# waveform_shield.net
KiCad netlist of a schematic drawn in EAGLE
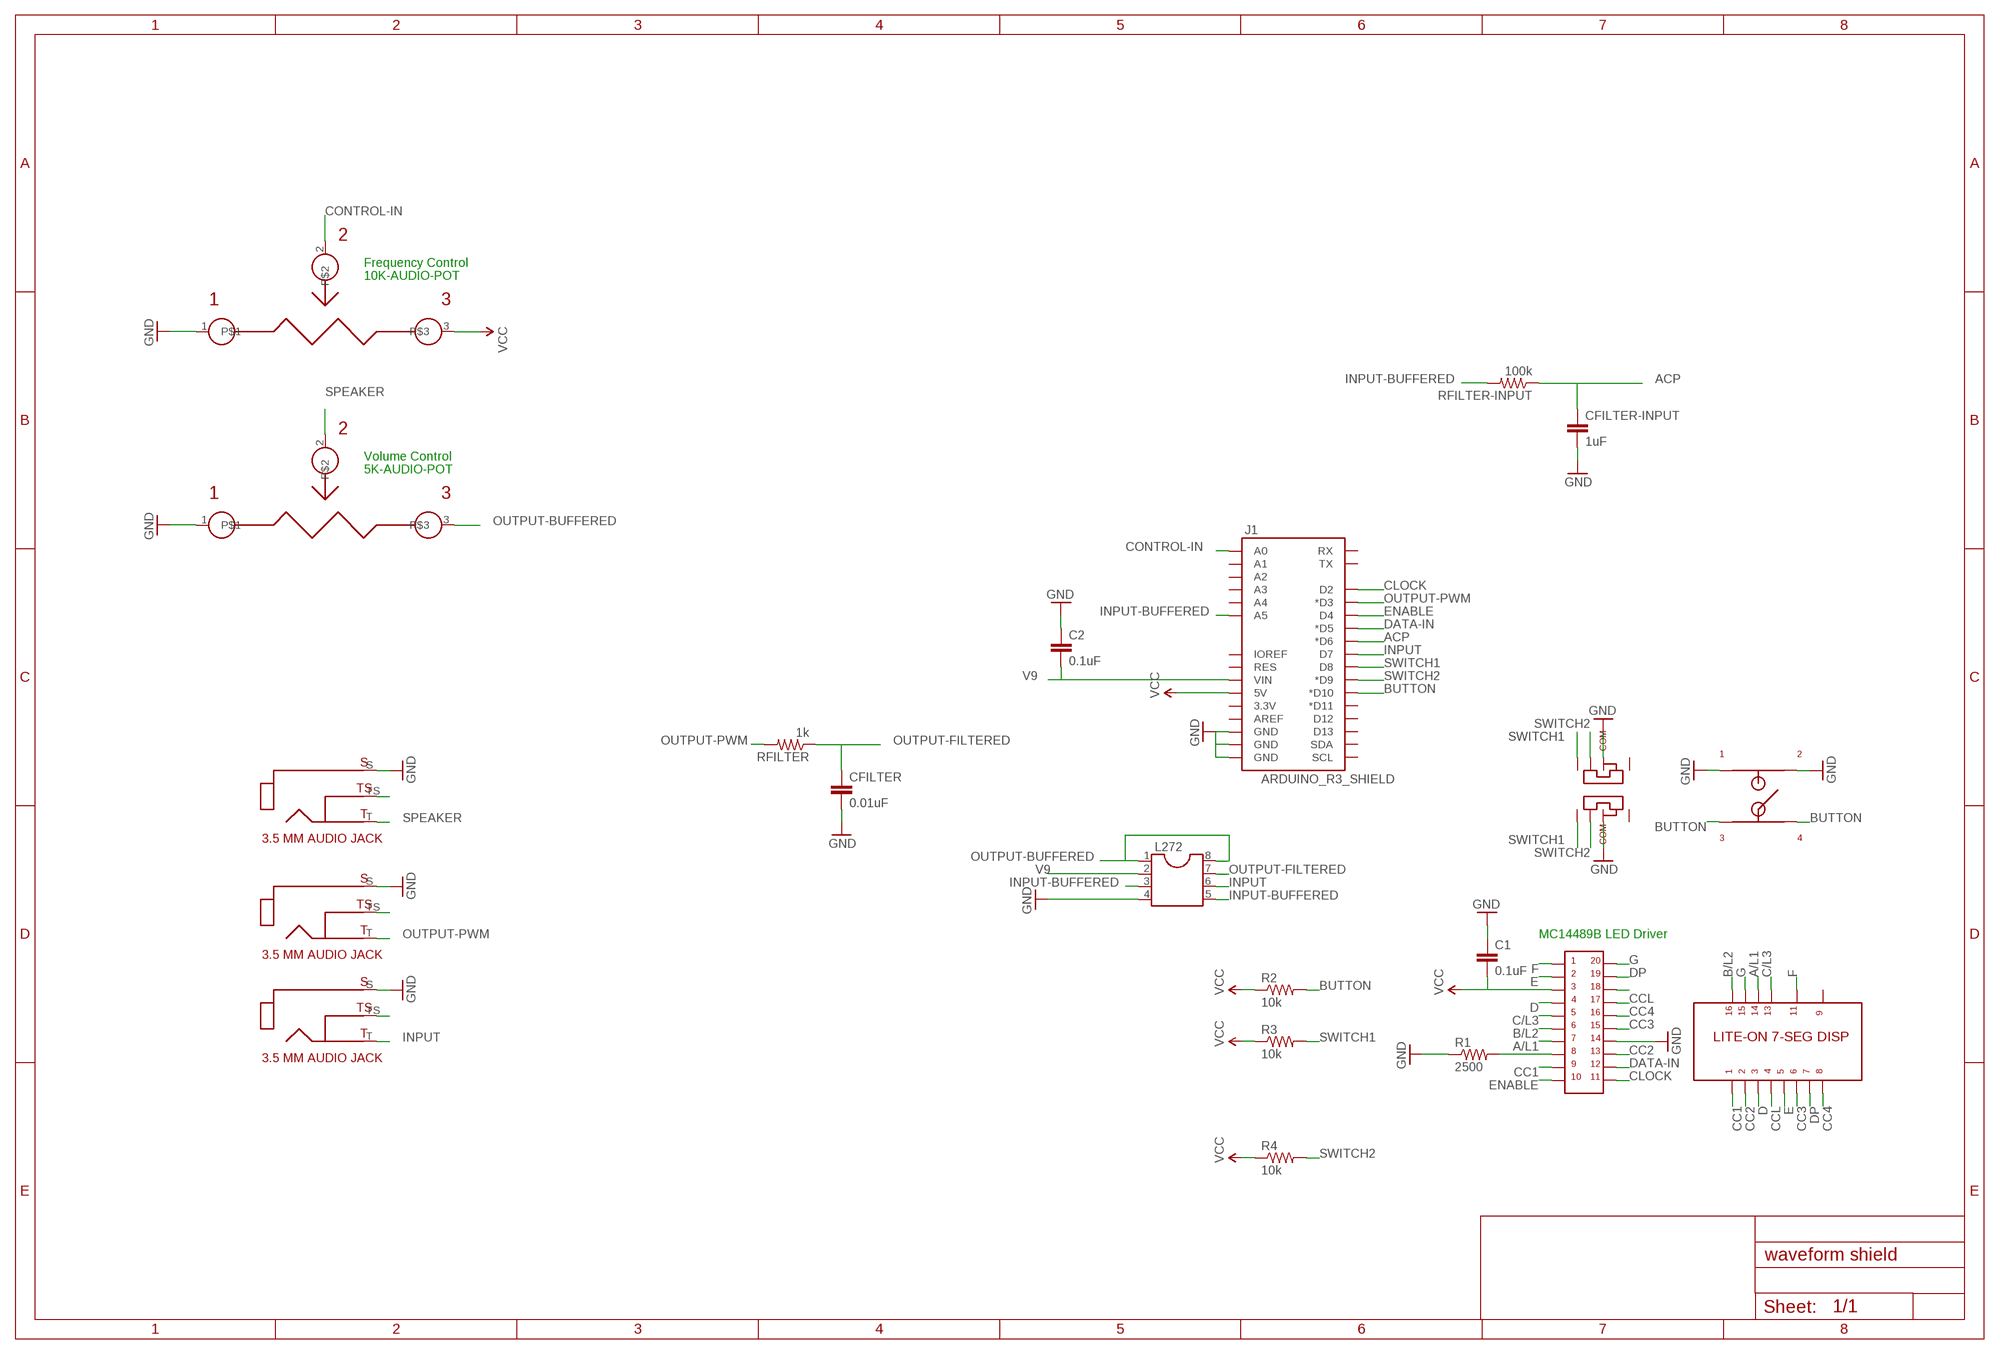
[diagram p0: schematic, sheet 1]

(export (version "E")
  (design (tool "Eeschema 10.0.6"))
  (components
    (comp (ref "5K-AUDIO-POT")
      (value "BOURNS-PTV09A-2")
      (footprint "eagle-import:BOURNS-POT-PTV09A-2")
      (libsource (lib "eagle-import") (part "BOURNS-PTV09A-2"))
    )
    (comp (ref "C1")
      (value "0.1uF")
      (footprint "eagle-import:CAP-PTH-SMALL")
      (libsource (lib "eagle-import") (part "CAPPTH"))
    )
    (comp (ref "C2")
      (value "0.1uF")
      (footprint "eagle-import:CAP-PTH-SMALL")
      (libsource (lib "eagle-import") (part "CAPPTH"))
    )
    (comp (ref "CFILTER")
      (value "0.01uF")
      (footprint "eagle-import:CAP-PTH-SMALL")
      (libsource (lib "eagle-import") (part "CAPPTH"))
    )
    (comp (ref "CFILTER-INPUT")
      (value "1uF")
      (footprint "eagle-import:CAP-PTH-SMALL")
      (libsource (lib "eagle-import") (part "CAPPTH"))
    )
    (comp (ref "J1")
      (value "ARDUINO_R3_SHIELD")
      (footprint "eagle-import:UNO_R3_SHIELD")
      (libsource (lib "eagle-import") (part "ARDUINO_R3_SHIELD"))
    )
    (comp (ref "L272")
      (value "DIL8")
      (footprint "eagle-import:DIL08")
      (libsource (lib "eagle-import") (part "DIL8"))
    )
    (comp (ref "R1")
      (value "2500")
      (footprint "eagle-import:AXIAL-0.3")
      (libsource (lib "eagle-import") (part "RESISTORAXIAL-0.3"))
    )
    (comp (ref "R2")
      (value "10k")
      (footprint "eagle-import:AXIAL-0.3")
      (libsource (lib "eagle-import") (part "SparkFun-Resistors_RESISTORAXIAL-0.3"))
    )
    (comp (ref "R3")
      (value "10k")
      (footprint "eagle-import:AXIAL-0.3")
      (libsource (lib "eagle-import") (part "SparkFun-Resistors_RESISTORAXIAL-0.3"))
    )
    (comp (ref "R4")
      (value "10k")
      (footprint "eagle-import:AXIAL-0.3")
      (libsource (lib "eagle-import") (part "SparkFun-Resistors_RESISTORAXIAL-0.3"))
    )
    (comp (ref "RFILTER")
      (value "1k")
      (footprint "eagle-import:AXIAL-0.3")
      (libsource (lib "eagle-import") (part "SparkFun-Resistors_RESISTORAXIAL-0.3"))
    )
    (comp (ref "RFILTER-INPUT")
      (value "100k")
      (footprint "eagle-import:AXIAL-0.3")
      (libsource (lib "eagle-import") (part "SparkFun-Resistors_RESISTORAXIAL-0.3"))
    )
    (comp (ref "U$1")
      (value "LITE-ON-7-SEG-DISP")
      (footprint "eagle-import:7-SEG-DISPLAY-LITE-ON")
      (libsource (lib "eagle-import") (part "LITE-ON-7-SEG-DISP"))
    )
    (comp (ref "U$2")
      (value "MC14489B-LED-DRIVER")
      (footprint "eagle-import:DIP-20")
      (libsource (lib "eagle-import") (part "MC14489B-LED-DRIVER"))
    )
    (comp (ref "U$3")
      (value "3.5MM-AUDIO-JACK-CUI")
      (footprint "eagle-import:3.5MM-AUDIO-JACK-MONO-CUI")
      (libsource (lib "eagle-import") (part "3.5MM-AUDIO-JACK-CUI"))
    )
    (comp (ref "U$4")
      (value "E-SWITCH-THREE-WAY-SWITCH")
      (footprint "eagle-import:EG2301-SLIDE-SWITCH")
      (libsource (lib "eagle-import") (part "E-SWITCH-THREE-WAY-SWITCH"))
    )
    (comp (ref "U$5")
      (value "SWITCH-MOMENTARY-ON-SCHURTER")
      (footprint "eagle-import:SWITCH-MOMENTARY-ON-SCHURTER")
      (libsource (lib "eagle-import") (part "SWITCH-MOMENTARY-ON-SCHURTER"))
    )
    (comp (ref "U$6")
      (value "3.5MM-AUDIO-JACK-CUI")
      (footprint "eagle-import:3.5MM-AUDIO-JACK-MONO-CUI")
      (libsource (lib "eagle-import") (part "3.5MM-AUDIO-JACK-CUI"))
    )
    (comp (ref "U$7")
      (value "3.5MM-AUDIO-JACK-CUI")
      (footprint "eagle-import:3.5MM-AUDIO-JACK-MONO-CUI")
      (libsource (lib "eagle-import") (part "3.5MM-AUDIO-JACK-CUI"))
    )
    (comp (ref "U$9")
      (value "BOURNS-PTV09A-2")
      (footprint "eagle-import:BOURNS-POT-PTV09A-2")
      (libsource (lib "eagle-import") (part "BOURNS-PTV09A-2"))
    )
  )
  (nets
    (net (code "1") (name "/ACP") (class "Default")
      (node (ref "CFILTER-INPUT") (pin "1") (pinfunction "1_1") (pintype "passive"))
      (node (ref "J1") (pin "D6") (pinfunction "*D6_D6") (pintype "bidirectional"))
      (node (ref "RFILTER-INPUT") (pin "P$1") (pinfunction "1_P$1") (pintype "passive"))
    )
    (net (code "2") (name "/A{slash}L1") (class "Default")
      (node (ref "U$1") (pin "P$14") (pinfunction "P$14_P$14") (pintype "bidirectional"))
      (node (ref "U$2") (pin "P$7") (pinfunction "P$7_P$7") (pintype "bidirectional"))
    )
    (net (code "3") (name "/BUTTON") (class "Default")
      (node (ref "J1") (pin "D10") (pinfunction "*D10_D10") (pintype "bidirectional"))
      (node (ref "R2") (pin "P$2") (pinfunction "2_P$2") (pintype "passive"))
      (node (ref "U$5") (pin "P$3") (pinfunction "P$3_P$3") (pintype "bidirectional"))
      (node (ref "U$5") (pin "P$4") (pinfunction "P$4_P$4") (pintype "bidirectional"))
    )
    (net (code "4") (name "/B{slash}L2") (class "Default")
      (node (ref "U$1") (pin "P$16") (pinfunction "P$16_P$16") (pintype "bidirectional"))
      (node (ref "U$2") (pin "P$6") (pinfunction "P$6_P$6") (pintype "bidirectional"))
    )
    (net (code "5") (name "/CC1") (class "Default")
      (node (ref "U$1") (pin "P$1") (pinfunction "P$1_P$1") (pintype "bidirectional"))
      (node (ref "U$2") (pin "P$9") (pinfunction "P$9_P$9") (pintype "bidirectional"))
    )
    (net (code "6") (name "/CC2") (class "Default")
      (node (ref "U$1") (pin "P$2") (pinfunction "P$2_P$2") (pintype "bidirectional"))
      (node (ref "U$2") (pin "P$13") (pinfunction "P$13_P$13") (pintype "bidirectional"))
    )
    (net (code "7") (name "/CC3") (class "Default")
      (node (ref "U$1") (pin "P$6") (pinfunction "P$6_P$6") (pintype "bidirectional"))
      (node (ref "U$2") (pin "P$15") (pinfunction "P$15_P$15") (pintype "bidirectional"))
    )
    (net (code "8") (name "/CC4") (class "Default")
      (node (ref "U$1") (pin "P$8") (pinfunction "P$8_P$8") (pintype "bidirectional"))
      (node (ref "U$2") (pin "P$16") (pinfunction "P$16_P$16") (pintype "bidirectional"))
    )
    (net (code "9") (name "/CCL") (class "Default")
      (node (ref "U$1") (pin "P$4") (pinfunction "P$4_P$4") (pintype "bidirectional"))
      (node (ref "U$2") (pin "P$17") (pinfunction "P$17_P$17") (pintype "bidirectional"))
    )
    (net (code "10") (name "/CLOCK") (class "Default")
      (node (ref "J1") (pin "D2") (pinfunction "D2_D2") (pintype "bidirectional"))
      (node (ref "U$2") (pin "P$11") (pinfunction "P$11_P$11") (pintype "bidirectional"))
    )
    (net (code "11") (name "/CONTROL-IN") (class "Default")
      (node (ref "J1") (pin "A0") (pinfunction "A0_A0") (pintype "bidirectional"))
      (node (ref "U$9") (pin "2") (pinfunction "P$2_2") (pintype "bidirectional"))
    )
    (net (code "12") (name "/C{slash}L3") (class "Default")
      (node (ref "U$1") (pin "P$13") (pinfunction "P$13_P$13") (pintype "bidirectional"))
      (node (ref "U$2") (pin "P$5") (pinfunction "P$5_P$5") (pintype "bidirectional"))
    )
    (net (code "13") (name "/D") (class "Default")
      (node (ref "U$1") (pin "P$3") (pinfunction "P$3_P$3") (pintype "bidirectional"))
      (node (ref "U$2") (pin "P$4") (pinfunction "P$4_P$4") (pintype "bidirectional"))
    )
    (net (code "14") (name "/DATA-IN") (class "Default")
      (node (ref "J1") (pin "D5") (pinfunction "*D5_D5") (pintype "bidirectional"))
      (node (ref "U$2") (pin "P$12") (pinfunction "P$12_P$12") (pintype "bidirectional"))
    )
    (net (code "15") (name "/DP") (class "Default")
      (node (ref "U$1") (pin "P$7") (pinfunction "P$7_P$7") (pintype "bidirectional"))
      (node (ref "U$2") (pin "P$19") (pinfunction "P$19_P$19") (pintype "bidirectional"))
    )
    (net (code "16") (name "/E") (class "Default")
      (node (ref "U$1") (pin "P$5") (pinfunction "P$5_P$5") (pintype "bidirectional"))
      (node (ref "U$2") (pin "P$2") (pinfunction "P$2_P$2") (pintype "bidirectional"))
    )
    (net (code "17") (name "/ENABLE") (class "Default")
      (node (ref "J1") (pin "D4") (pinfunction "D4_D4") (pintype "bidirectional"))
      (node (ref "U$2") (pin "P$10") (pinfunction "P$10_P$10") (pintype "bidirectional"))
    )
    (net (code "18") (name "/F") (class "Default")
      (node (ref "U$1") (pin "P$11") (pinfunction "P$11_P$11") (pintype "bidirectional"))
      (node (ref "U$2") (pin "P$1") (pinfunction "P$1_P$1") (pintype "bidirectional"))
    )
    (net (code "19") (name "/G") (class "Default")
      (node (ref "U$1") (pin "P$15") (pinfunction "P$15_P$15") (pintype "bidirectional"))
      (node (ref "U$2") (pin "P$20") (pinfunction "P$20_P$20") (pintype "bidirectional"))
    )
    (net (code "20") (name "/INPUT") (class "Default")
      (node (ref "J1") (pin "D7") (pinfunction "D7_D7") (pintype "bidirectional"))
      (node (ref "L272") (pin "6") (pinfunction "6_6") (pintype "passive"))
      (node (ref "U$7") (pin "T") (pinfunction "T_T") (pintype "bidirectional"))
    )
    (net (code "21") (name "/INPUT-BUFFERED") (class "Default")
      (node (ref "J1") (pin "A5") (pinfunction "A5_A5") (pintype "bidirectional"))
      (node (ref "L272") (pin "3") (pinfunction "3_3") (pintype "passive"))
      (node (ref "L272") (pin "5") (pinfunction "5_5") (pintype "passive"))
      (node (ref "RFILTER-INPUT") (pin "P$2") (pinfunction "2_P$2") (pintype "passive"))
    )
    (net (code "22") (name "/OUTPUT-BUFFERED") (class "Default")
      (node (ref "5K-AUDIO-POT") (pin "3") (pinfunction "P$3_3") (pintype "bidirectional"))
      (node (ref "L272") (pin "1") (pinfunction "1_1") (pintype "passive"))
      (node (ref "L272") (pin "8") (pinfunction "8_8") (pintype "passive"))
    )
    (net (code "23") (name "/OUTPUT-FILTERED") (class "Default")
      (node (ref "CFILTER") (pin "1") (pinfunction "1_1") (pintype "passive"))
      (node (ref "L272") (pin "7") (pinfunction "7_7") (pintype "passive"))
      (node (ref "RFILTER") (pin "P$1") (pinfunction "1_P$1") (pintype "passive"))
    )
    (net (code "24") (name "/OUTPUT-PWM") (class "Default")
      (node (ref "J1") (pin "D3") (pinfunction "*D3_D3") (pintype "bidirectional"))
      (node (ref "RFILTER") (pin "P$2") (pinfunction "2_P$2") (pintype "passive"))
      (node (ref "U$6") (pin "T") (pinfunction "T_T") (pintype "bidirectional"))
    )
    (net (code "25") (name "/SPEAKER") (class "Default")
      (node (ref "5K-AUDIO-POT") (pin "2") (pinfunction "P$2_2") (pintype "bidirectional"))
      (node (ref "U$3") (pin "T") (pinfunction "T_T") (pintype "bidirectional"))
    )
    (net (code "26") (name "/SWITCH1") (class "Default")
      (node (ref "J1") (pin "D8") (pinfunction "D8_D8") (pintype "bidirectional"))
      (node (ref "R3") (pin "P$2") (pinfunction "2_P$2") (pintype "passive"))
      (node (ref "U$4") (pin "P$1") (pinfunction "P$1_P$1") (pintype "bidirectional"))
      (node (ref "U$4") (pin "P$5") (pinfunction "P$5_P$5") (pintype "bidirectional"))
    )
    (net (code "27") (name "/SWITCH2") (class "Default")
      (node (ref "J1") (pin "D9") (pinfunction "*D9_D9") (pintype "bidirectional"))
      (node (ref "R4") (pin "P$2") (pinfunction "2_P$2") (pintype "passive"))
      (node (ref "U$4") (pin "P$2") (pinfunction "P$2_P$2") (pintype "bidirectional"))
      (node (ref "U$4") (pin "P$6") (pinfunction "P$6_P$6") (pintype "bidirectional"))
    )
    (net (code "28") (name "/V9") (class "Default")
      (node (ref "C2") (pin "2") (pinfunction "2_2") (pintype "passive"))
      (node (ref "J1") (pin "VIN") (pinfunction "VIN_VIN") (pintype "bidirectional"))
      (node (ref "L272") (pin "2") (pinfunction "2_2") (pintype "passive"))
    )
    (net (code "29") (name "GND") (class "Default")
      (node (ref "5K-AUDIO-POT") (pin "1") (pinfunction "P$1_1") (pintype "bidirectional"))
      (node (ref "C1") (pin "1") (pinfunction "1_1") (pintype "passive"))
      (node (ref "C2") (pin "1") (pinfunction "1_1") (pintype "passive"))
      (node (ref "CFILTER") (pin "2") (pinfunction "2_2") (pintype "passive"))
      (node (ref "CFILTER-INPUT") (pin "2") (pinfunction "2_2") (pintype "passive"))
      (node (ref "J1") (pin "GND@0") (pinfunction "GND_GND@0") (pintype "bidirectional"))
      (node (ref "J1") (pin "GND@1") (pinfunction "GND_GND@1") (pintype "bidirectional"))
      (node (ref "J1") (pin "GND@2") (pinfunction "GND_GND@2") (pintype "bidirectional"))
      (node (ref "L272") (pin "4") (pinfunction "4_4") (pintype "passive"))
      (node (ref "R1") (pin "P$1") (pinfunction "1_P$1") (pintype "passive"))
      (node (ref "U$2") (pin "P$14") (pinfunction "P$14_P$14") (pintype "bidirectional"))
      (node (ref "U$3") (pin "S") (pinfunction "S_S") (pintype "bidirectional"))
      (node (ref "U$4") (pin "P$3") (pinfunction "P$3_P$3") (pintype "bidirectional"))
      (node (ref "U$4") (pin "P$7") (pinfunction "P$7_P$7") (pintype "bidirectional"))
      (node (ref "U$5") (pin "P$1") (pinfunction "P$1_P$1") (pintype "bidirectional"))
      (node (ref "U$5") (pin "P$2") (pinfunction "P$2_P$2") (pintype "bidirectional"))
      (node (ref "U$6") (pin "S") (pinfunction "S_S") (pintype "bidirectional"))
      (node (ref "U$7") (pin "S") (pinfunction "S_S") (pintype "bidirectional"))
      (node (ref "U$9") (pin "1") (pinfunction "P$1_1") (pintype "bidirectional"))
    )
    (net (code "30") (name "Net-(R1-2)") (class "Default")
      (node (ref "R1") (pin "P$2") (pinfunction "2_P$2") (pintype "passive"))
      (node (ref "U$2") (pin "P$8") (pinfunction "P$8_P$8") (pintype "bidirectional"))
    )
    (net (code "31") (name "VCC") (class "Default")
      (node (ref "C1") (pin "2") (pinfunction "2_2") (pintype "passive"))
      (node (ref "J1") (pin "5V") (pinfunction "5V_5V") (pintype "bidirectional"))
      (node (ref "R2") (pin "P$1") (pinfunction "1_P$1") (pintype "passive"))
      (node (ref "R3") (pin "P$1") (pinfunction "1_P$1") (pintype "passive"))
      (node (ref "R4") (pin "P$1") (pinfunction "1_P$1") (pintype "passive"))
      (node (ref "U$2") (pin "P$3") (pinfunction "P$3_P$3") (pintype "bidirectional"))
      (node (ref "U$9") (pin "3") (pinfunction "P$3_3") (pintype "bidirectional"))
    )
    (net (code "32") (name "unconnected-(J1-*D11-PadD11)") (class "Default")
      (node (ref "J1") (pin "D11") (pinfunction "*D11_D11") (pintype "bidirectional"))
    )
    (net (code "33") (name "unconnected-(J1-Pad3.3V)") (class "Default")
      (node (ref "J1") (pin "3.3V") (pinfunction "3.3V_3.3V") (pintype "bidirectional"))
    )
    (net (code "34") (name "unconnected-(J1-PadA1)") (class "Default")
      (node (ref "J1") (pin "A1") (pinfunction "A1_A1") (pintype "bidirectional"))
    )
    (net (code "35") (name "unconnected-(J1-PadA2)") (class "Default")
      (node (ref "J1") (pin "A2") (pinfunction "A2_A2") (pintype "bidirectional"))
    )
    (net (code "36") (name "unconnected-(J1-PadA3)") (class "Default")
      (node (ref "J1") (pin "A3") (pinfunction "A3_A3") (pintype "bidirectional"))
    )
    (net (code "37") (name "unconnected-(J1-PadA4)") (class "Default")
      (node (ref "J1") (pin "A4") (pinfunction "A4_A4") (pintype "bidirectional"))
    )
    (net (code "38") (name "unconnected-(J1-PadAREF)") (class "Default")
      (node (ref "J1") (pin "AREF") (pinfunction "AREF_AREF") (pintype "bidirectional"))
    )
    (net (code "39") (name "unconnected-(J1-PadD12)") (class "Default")
      (node (ref "J1") (pin "D12") (pinfunction "D12_D12") (pintype "bidirectional"))
    )
    (net (code "40") (name "unconnected-(J1-PadD13)") (class "Default")
      (node (ref "J1") (pin "D13") (pinfunction "D13_D13") (pintype "bidirectional"))
    )
    (net (code "41") (name "unconnected-(J1-PadIOREF)") (class "Default")
      (node (ref "J1") (pin "IOREF") (pinfunction "IOREF_IOREF") (pintype "bidirectional"))
    )
    (net (code "42") (name "unconnected-(J1-PadRES)") (class "Default")
      (node (ref "J1") (pin "RES") (pinfunction "RES_RES") (pintype "bidirectional"))
    )
    (net (code "43") (name "unconnected-(J1-PadRX)") (class "Default")
      (node (ref "J1") (pin "RX") (pinfunction "RX_RX") (pintype "bidirectional"))
    )
    (net (code "44") (name "unconnected-(J1-PadSCL)") (class "Default")
      (node (ref "J1") (pin "SCL") (pinfunction "SCL_SCL") (pintype "bidirectional"))
    )
    (net (code "45") (name "unconnected-(J1-PadSDA)") (class "Default")
      (node (ref "J1") (pin "SDA") (pinfunction "SDA_SDA") (pintype "bidirectional"))
    )
    (net (code "46") (name "unconnected-(J1-PadTX)") (class "Default")
      (node (ref "J1") (pin "TX") (pinfunction "TX_TX") (pintype "bidirectional"))
    )
    (net (code "47") (name "unconnected-(U$1-PadP$9)") (class "Default")
      (node (ref "U$1") (pin "P$9") (pinfunction "P$9_P$9") (pintype "bidirectional"))
    )
    (net (code "48") (name "unconnected-(U$2-PadP$18)") (class "Default")
      (node (ref "U$2") (pin "P$18") (pinfunction "P$18_P$18") (pintype "bidirectional"))
    )
    (net (code "49") (name "unconnected-(U$3-PadTS)") (class "Default")
      (node (ref "U$3") (pin "TS") (pinfunction "TS_TS") (pintype "bidirectional"))
    )
    (net (code "50") (name "unconnected-(U$4-PadP$4)") (class "Default")
      (node (ref "U$4") (pin "P$4") (pinfunction "P$4_P$4") (pintype "bidirectional"))
    )
    (net (code "51") (name "unconnected-(U$4-PadP$8)") (class "Default")
      (node (ref "U$4") (pin "P$8") (pinfunction "P$8_P$8") (pintype "bidirectional"))
    )
    (net (code "52") (name "unconnected-(U$6-PadTS)") (class "Default")
      (node (ref "U$6") (pin "TS") (pinfunction "TS_TS") (pintype "bidirectional"))
    )
    (net (code "53") (name "unconnected-(U$7-PadTS)") (class "Default")
      (node (ref "U$7") (pin "TS") (pinfunction "TS_TS") (pintype "bidirectional"))
    )
  )
)
